# Power.net
KiCad netlist of a schematic drawn in Altium Designer
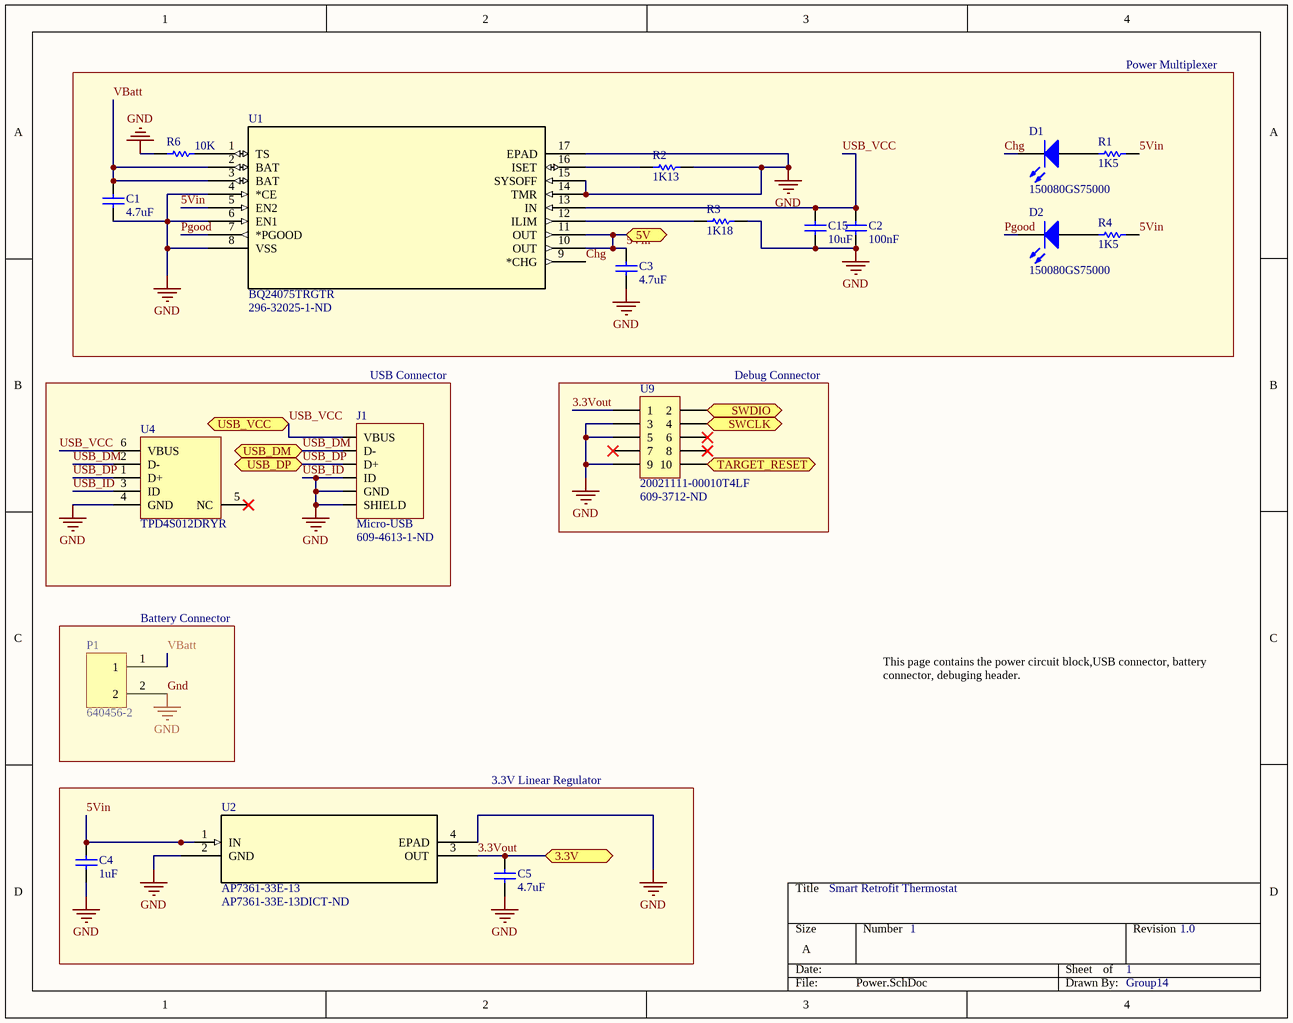
[diagram p0: Power.SchDoc]

(export (version "E")
  (design (tool "Eeschema 10.0.6"))
  (components
    (comp (ref "C1")
      (value "4.7uF")
      (footprint "CAPC0805(2012)155_L")
      (description "CAP 4.7uF 10V ±10% 0805 (2012 Metric) Thickness 1.55mm SMD")
      (fields (field (name "TOLERANCE") "Â±10%"))
      (libsource (lib "Altium Content Vault") (part "CAP"))
    )
    (comp (ref "C2")
      (value "100nF")
      (footprint "CAPC0805(2012)100_L")
      (description "CAP 100nF 16V -20% to +80% 0805 (2012 Metric) Thickness 1mm SMD")
      (fields (field (name "TOLERANCE") "-20% to +80%"))
      (libsource (lib "Altium Content Vault") (part "CMP-1036-04407-1"))
    )
    (comp (ref "C3")
      (value "4.7uF")
      (footprint "CAPC0805(2012)155_L")
      (description "CAP 4.7uF 10V ±10% 0805 (2012 Metric) Thickness 1.55mm SMD")
      (fields (field (name "TOLERANCE") "Â±10%"))
      (libsource (lib "Altium Content Vault") (part "CAP"))
    )
    (comp (ref "C4")
      (value "1uF")
      (footprint "CAPC0805(2012)100_L")
      (description "CAP 1uF 6.3V ±20% 0805 (2012 Metric) Thickness 1mm SMD")
      (fields (field (name "TOLERANCE") "Â±20%"))
      (libsource (lib "Altium Content Vault") (part "CAP"))
    )
    (comp (ref "C5")
      (value "4.7uF")
      (footprint "CAPC0805(2012)155_L")
      (description "CAP 4.7uF 10V ±10% 0805 (2012 Metric) Thickness 1.55mm SMD")
      (fields (field (name "TOLERANCE") "Â±10%"))
      (libsource (lib "Altium Content Vault") (part "CAP"))
    )
    (comp (ref "C15")
      (value "10uF")
      (footprint "CAPC0805(2012)100_L")
      (description "CAP 10uF 16V ±20% 0805 (2012 Metric) Thickness 1mm SMD")
      (fields (field (name "TOLERANCE") "Â±20%"))
      (libsource (lib "Altium Content Vault") (part "CMP-1036-04930-1"))
    )
    (comp (ref "D1")
      (value "150080GS75000")
      (footprint "0805_A")
      (description "SMD mono-color Chip LED, WL-SMCW, Green")
      (fields (field (name "MANUFACTURER") "Wuerth Elektronik"))
      (libsource (lib "Altium Content Vault") (part "WE-LED_K1A2-2"))
    )
    (comp (ref "D2")
      (value "150080GS75000")
      (footprint "0805_A")
      (description "SMD mono-color Chip LED, WL-SMCW, Green")
      (fields (field (name "MANUFACTURER") "Wuerth Elektronik"))
      (libsource (lib "Altium Content Vault") (part "WE-LED_K1A2-2"))
    )
    (comp (ref "J1")
      (value "Micro-USB")
      (footprint "10118192-0001LF")
      (description "CONN USB MICRO B RECPT SMT R/A")
      (fields (field (name "SUPPLIER PART NUMBER 1") "609-4613-1-ND"))
      (libsource (lib "ese516_baseComponents") (part "10118192-0001LF"))
    )
    (comp (ref "P1")
      (value "640456-2")
      (footprint "640456-2")
      (description "CONN HEADER VERT 2POS .100 TIN")
      (fields (field (name "MANUFACTURER") "TE Connectivity"))
      (libsource (lib "ese516_baseComponents") (part "640456-2"))
    )
    (comp (ref "R1")
      (value "1K5")
      (footprint "RESC0805(2012)_M")
      (description "1K5 0.125W 1% 0805 (2012 Metric)  SMD")
      (fields (field (name "POWER") "0.125 W") (field (name "TOLERANCE") "1 %"))
      (libsource (lib "Altium Content Vault") (part "CMP-1013-00528-1"))
    )
    (comp (ref "R2")
      (value "1K13")
      (footprint "RESC0805(2012)_L")
      (description "1K13 0.125W 1% 0805 (2012 Metric)  SMD")
      (fields (field (name "TOLERANCE") "1 %") (field (name "POWER") "0.125 W"))
      (libsource (lib "Altium Content Vault") (part "RES"))
    )
    (comp (ref "R3")
      (value "1K18")
      (footprint "RESC0805(2012)_M")
      (description "1K18 0.125W 1% 0805 (2012 Metric)  SMD")
      (fields (field (name "TOLERANCE") "1 %") (field (name "POWER") "0.125 W"))
      (libsource (lib "Altium Content Vault") (part "CMP-1013-00517-1"))
    )
    (comp (ref "R4")
      (value "1K5")
      (footprint "RESC0805(2012)_M")
      (description "1K5 0.125W 1% 0805 (2012 Metric)  SMD")
      (fields (field (name "POWER") "0.125 W") (field (name "TOLERANCE") "1 %"))
      (libsource (lib "Altium Content Vault") (part "RES"))
    )
    (comp (ref "R6")
      (value "10K")
      (footprint "RESC0805(2012)_M")
      (description "10K 0.125W 1% 0805 (2012 Metric)  SMD")
      (fields (field (name "POWER") "0.125 W") (field (name "TOLERANCE") "1 %"))
      (libsource (lib "Altium Content Vault") (part "RES"))
    )
    (comp (ref "U1")
      (value "BQ24075TRGTR")
      (footprint "RGT16_1P7X1P7")
      (description "Imported")
      (fields
        (field (name "MANUFACTURER") "Texas Instruments")
        (field (name "SUPPLIER PART NUMBER 1") "296-32025-1-ND")
      )
      (libsource (lib "ese516_baseComponents") (part "BQ24075TRGTR"))
    )
    (comp (ref "U2")
      (value "AP7361-33E-13")
      (footprint "SOT-223")
      (description "Imported")
      (fields (field (name "SUPPLIER PART NUMBER 1") "AP7361-33E-13DICT-ND"))
      (libsource (lib "ese516_baseComponents") (part "AP7361-33E-13"))
    )
    (comp (ref "U4")
      (value "TPD4S012DRYR")
      (footprint "DRY0006A")
      (fields (field (name "MANUFACTURER") "Texas Instruments"))
      (libsource (lib "Altium Content Vault") (part "TI-TPD4S012-SON_DRY-6"))
    )
    (comp (ref "U9")
      (value "20021111-00010T4LF")
      (footprint "20021111-00010T4LF")
      (description "CONN HEADER 10POS UNSHD VERT T/H")
      (fields
        (field (name "MANUFACTURER") "Amphenol / FCI")
        (field (name "SUPPLIER PART NUMBER 1") "609-3712-ND")
      )
      (libsource (lib "ese516_baseComponents") (part "20021111-00010T4LF"))
    )
  )
  (nets
    (net (code "1") (name "/3.3Vout") (class "Default")
      (node (ref "C5") (pin "2") (pinfunction "2_2") (pintype "passive"))
      (node (ref "U2") (pin "3") (pinfunction "OUT_3") (pintype "power_in"))
      (node (ref "U9") (pin "1") (pinfunction "1_1") (pintype "passive"))
    )
    (net (code "2") (name "/5Vin") (class "Default")
      (node (ref "C3") (pin "2") (pinfunction "2_2") (pintype "passive"))
      (node (ref "C4") (pin "2") (pinfunction "2_2") (pintype "passive"))
      (node (ref "R1") (pin "2") (pinfunction "2_2") (pintype "passive"))
      (node (ref "R4") (pin "2") (pinfunction "2_2") (pintype "passive"))
      (node (ref "U1") (pin "10") (pinfunction "OUT_10") (pintype "output"))
      (node (ref "U1") (pin "11") (pinfunction "OUT_11") (pintype "output"))
      (node (ref "U1") (pin "5") (pinfunction "EN2_5") (pintype "input"))
      (node (ref "U2") (pin "1") (pinfunction "IN_1") (pintype "input"))
    )
    (net (code "3") (name "/Chg") (class "Default")
      (node (ref "D1") (pin "1") (pinfunction "K_1") (pintype "passive"))
      (node (ref "U1") (pin "9") (pinfunction "*CHG_9") (pintype "output"))
    )
    (net (code "4") (name "/Pgood") (class "Default")
      (node (ref "D2") (pin "1") (pinfunction "K_1") (pintype "passive"))
      (node (ref "U1") (pin "7") (pinfunction "*PGOOD_7") (pintype "output"))
    )
    (net (code "5") (name "/SWCLK") (class "Default")
      (node (ref "U9") (pin "4") (pinfunction "4_4") (pintype "passive"))
    )
    (net (code "6") (name "/SWDIO") (class "Default")
      (node (ref "U9") (pin "2") (pinfunction "2_2") (pintype "passive"))
    )
    (net (code "7") (name "/TARGET_RESET") (class "Default")
      (node (ref "U9") (pin "10") (pinfunction "10_10") (pintype "passive"))
    )
    (net (code "8") (name "/USB_DM") (class "Default")
      (node (ref "J1") (pin "2") (pinfunction "D-_2") (pintype "passive"))
      (node (ref "U4") (pin "2") (pinfunction "D-_2") (pintype "passive"))
    )
    (net (code "9") (name "/USB_DP") (class "Default")
      (node (ref "J1") (pin "3") (pinfunction "D+_3") (pintype "passive"))
      (node (ref "U4") (pin "1") (pinfunction "D+_1") (pintype "passive"))
    )
    (net (code "10") (name "/USB_VCC") (class "Default")
      (node (ref "C15") (pin "2") (pinfunction "2_2") (pintype "passive"))
      (node (ref "C2") (pin "2") (pinfunction "2_2") (pintype "passive"))
      (node (ref "J1") (pin "1") (pinfunction "VBUS_1") (pintype "passive"))
      (node (ref "U1") (pin "13") (pinfunction "IN_13") (pintype "input"))
      (node (ref "U4") (pin "6") (pinfunction "VBUS_6") (pintype "passive"))
    )
    (net (code "11") (name "/VBatt") (class "Default")
      (node (ref "C1") (pin "2") (pinfunction "2_2") (pintype "passive"))
      (node (ref "P1") (pin "1") (pinfunction "1_1") (pintype "passive"))
      (node (ref "U1") (pin "2") (pinfunction "BAT_2") (pintype "bidirectional"))
      (node (ref "U1") (pin "3") (pinfunction "BAT_3") (pintype "bidirectional"))
    )
    (net (code "12") (name "GND") (class "Default")
      (node (ref "C1") (pin "1") (pinfunction "1_1") (pintype "passive"))
      (node (ref "C15") (pin "1") (pinfunction "1_1") (pintype "passive"))
      (node (ref "C2") (pin "1") (pinfunction "1_1") (pintype "passive"))
      (node (ref "C3") (pin "1") (pinfunction "1_1") (pintype "passive"))
      (node (ref "C4") (pin "1") (pinfunction "1_1") (pintype "passive"))
      (node (ref "C5") (pin "1") (pinfunction "1_1") (pintype "passive"))
      (node (ref "J1") (pin "4") (pinfunction "ID_4") (pintype "passive"))
      (node (ref "J1") (pin "5") (pinfunction "GND_5") (pintype "passive"))
      (node (ref "J1") (pin "6") (pinfunction "SHIELD_6") (pintype "passive"))
      (node (ref "P1") (pin "2") (pinfunction "2_2") (pintype "passive"))
      (node (ref "R2") (pin "2") (pinfunction "2_2") (pintype "passive"))
      (node (ref "R3") (pin "2") (pinfunction "2_2") (pintype "passive"))
      (node (ref "R6") (pin "1") (pinfunction "1_1") (pintype "passive"))
      (node (ref "U1") (pin "14") (pinfunction "TMR_14") (pintype "input"))
      (node (ref "U1") (pin "15") (pinfunction "SYSOFF_15") (pintype "input"))
      (node (ref "U1") (pin "17") (pinfunction "EPAD_17") (pintype "power_in"))
      (node (ref "U1") (pin "4") (pinfunction "*CE_4") (pintype "input"))
      (node (ref "U1") (pin "6") (pinfunction "EN1_6") (pintype "input"))
      (node (ref "U1") (pin "8") (pinfunction "VSS_8") (pintype "power_in"))
      (node (ref "U2") (pin "2") (pinfunction "GND_2") (pintype "power_in"))
      (node (ref "U2") (pin "4") (pinfunction "EPAD_4") (pintype "passive"))
      (node (ref "U4") (pin "3") (pinfunction "ID_3") (pintype "passive"))
      (node (ref "U4") (pin "4") (pinfunction "GND_4") (pintype "power_in"))
      (node (ref "U9") (pin "3") (pinfunction "3_3") (pintype "passive"))
      (node (ref "U9") (pin "5") (pinfunction "5_5") (pintype "passive"))
      (node (ref "U9") (pin "9") (pinfunction "9_9") (pintype "passive"))
    )
    (net (code "13") (name "Net-(D1-A)") (class "Default")
      (node (ref "D1") (pin "2") (pinfunction "A_2") (pintype "passive"))
      (node (ref "R1") (pin "1") (pinfunction "1_1") (pintype "passive"))
    )
    (net (code "14") (name "Net-(D2-A)") (class "Default")
      (node (ref "D2") (pin "2") (pinfunction "A_2") (pintype "passive"))
      (node (ref "R4") (pin "1") (pinfunction "1_1") (pintype "passive"))
    )
    (net (code "15") (name "Net-(U1-ILIM)") (class "Default")
      (node (ref "R3") (pin "1") (pinfunction "1_1") (pintype "passive"))
      (node (ref "U1") (pin "12") (pinfunction "ILIM_12") (pintype "output"))
    )
    (net (code "16") (name "Net-(U1-ISET)") (class "Default")
      (node (ref "R2") (pin "1") (pinfunction "1_1") (pintype "passive"))
      (node (ref "U1") (pin "16") (pinfunction "ISET_16") (pintype "bidirectional"))
    )
    (net (code "17") (name "Net-(U1-TS)") (class "Default")
      (node (ref "R6") (pin "2") (pinfunction "2_2") (pintype "passive"))
      (node (ref "U1") (pin "1") (pinfunction "TS_1") (pintype "bidirectional"))
    )
    (net (code "18") (name "unconnected-(U4-NC-Pad5)") (class "Default")
      (node (ref "U4") (pin "5") (pinfunction "NC_5") (pintype "passive+no_connect"))
    )
    (net (code "19") (name "unconnected-(U9-Pad6)") (class "Default")
      (node (ref "U9") (pin "6") (pinfunction "6_6") (pintype "passive+no_connect"))
    )
    (net (code "20") (name "unconnected-(U9-Pad7)") (class "Default")
      (node (ref "U9") (pin "7") (pinfunction "7_7") (pintype "passive+no_connect"))
    )
    (net (code "21") (name "unconnected-(U9-Pad8)") (class "Default")
      (node (ref "U9") (pin "8") (pinfunction "8_8") (pintype "passive+no_connect"))
    )
  )
)
